# ESP32-C3.net
KiCad netlist of a schematic drawn in Altium Designer
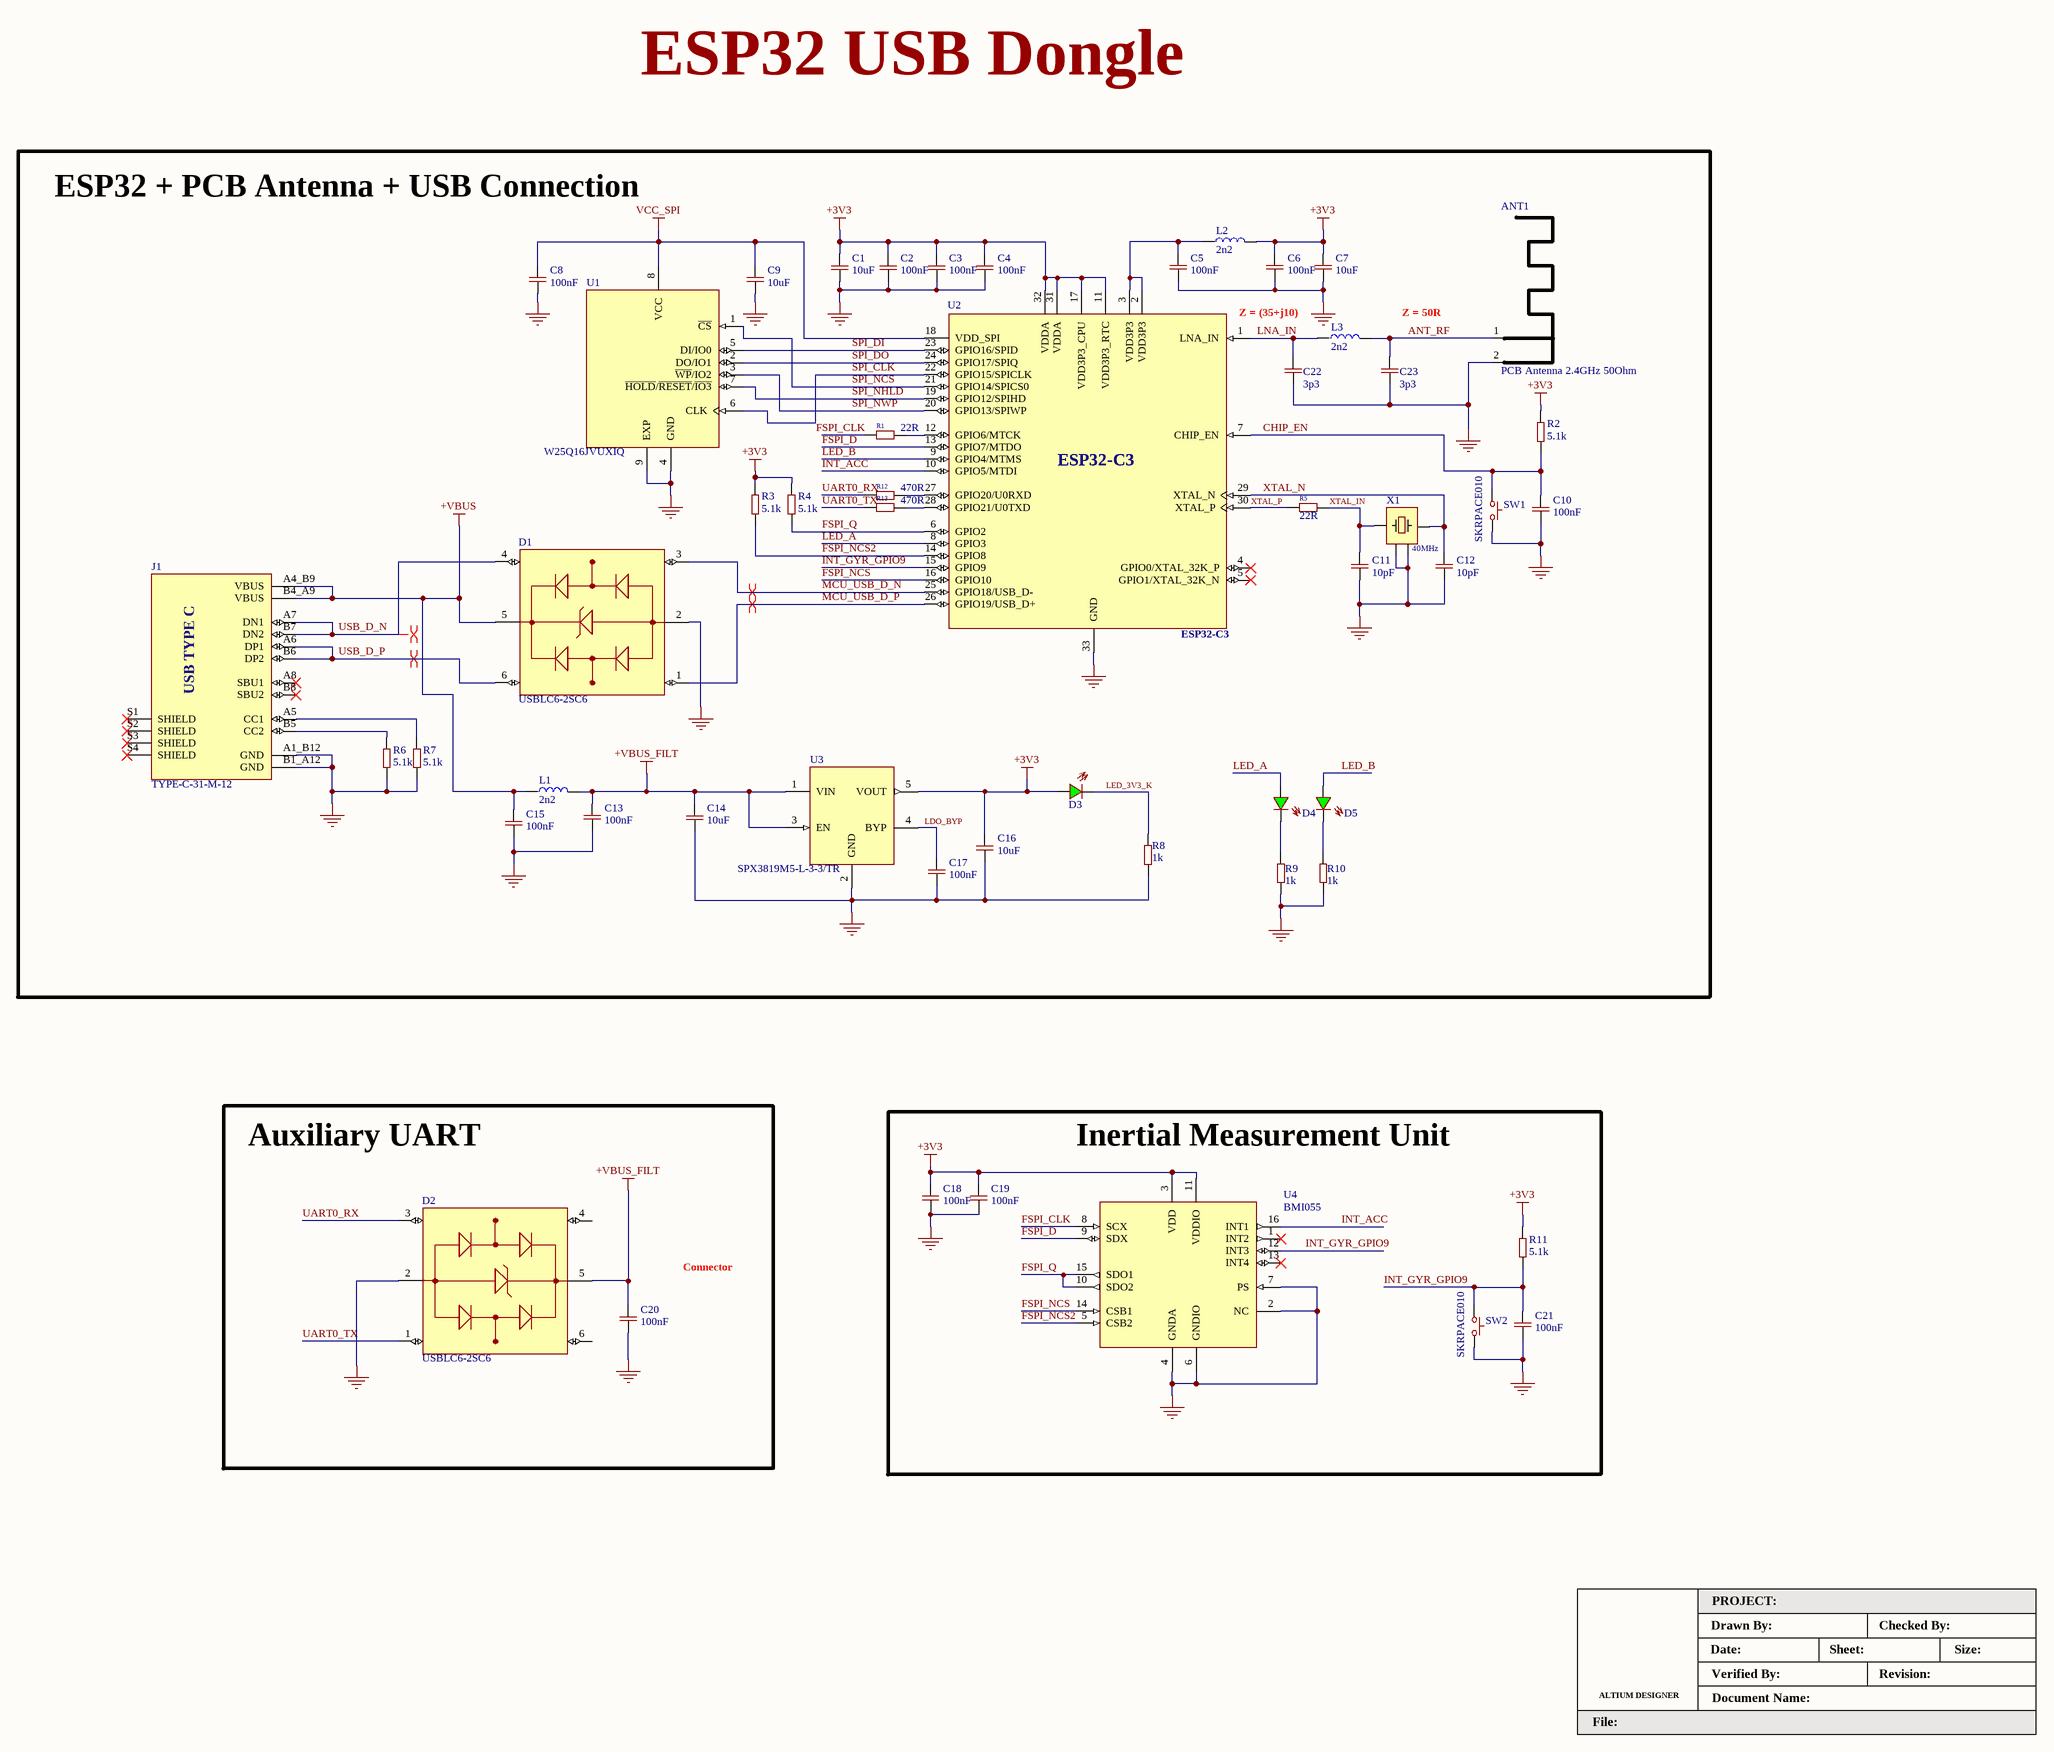
[diagram p0: ESP32-C3.SchDoc]

(export (version "E")
  (design (tool "Eeschema 10.0.6"))
  (components
    (comp (ref "ANT1")
      (value "PCB Antenna 2.4GHz 50Ohm")
      (footprint "ANT_IFA_USB_2_4GHz_50R")
      (description "Inverted F 2.4GHz ISM PCB Antenna 50Ohm")
      (libsource (lib "Schlib_ESP32C3") (part "ANT_IFA_USB_2_4GHz_50R"))
    )
    (comp (ref "C1")
      (value "10uF")
      (footprint "CAP_0603")
      (fields
        (field (name "MANUFACTURER") "Samsung Electro-Mechanics")
        (field (name "MANUFACTURER PART NUMBER") "CL10A106KP8NNNC")
        (field (name "TOLERANCE") "10%")
      )
      (libsource (lib "Schlib_ESP32C3") (part "CAP_0603"))
    )
    (comp (ref "C2")
      (value "100nF")
      (footprint "CAP_0402")
      (fields
        (field (name "MANUFACTURER") "Samsung Electro-Mechanics")
        (field (name "MANUFACTURER PART NUMBER") "CL05B104KO5NNNC")
        (field (name "TOLERANCE") "10%")
      )
      (libsource (lib "Schlib_ESP32C3") (part "CAP_0402"))
    )
    (comp (ref "C3")
      (value "100nF")
      (footprint "CAP_0402")
      (fields
        (field (name "MANUFACTURER") "Samsung Electro-Mechanics")
        (field (name "MANUFACTURER PART NUMBER") "CL05B104KO5NNNC")
        (field (name "TOLERANCE") "10%")
      )
      (libsource (lib "Schlib_ESP32C3") (part "CAP_0402"))
    )
    (comp (ref "C4")
      (value "100nF")
      (footprint "CAP_0402")
      (fields
        (field (name "MANUFACTURER") "Samsung Electro-Mechanics")
        (field (name "MANUFACTURER PART NUMBER") "CL05B104KO5NNNC")
        (field (name "TOLERANCE") "10%")
      )
      (libsource (lib "Schlib_ESP32C3") (part "CAP_0402"))
    )
    (comp (ref "C5")
      (value "100nF")
      (footprint "CAP_0402")
      (fields
        (field (name "MANUFACTURER") "Samsung Electro-Mechanics")
        (field (name "MANUFACTURER PART NUMBER") "CL05B104KO5NNNC")
        (field (name "TOLERANCE") "10%")
      )
      (libsource (lib "Schlib_ESP32C3") (part "CAP_0402"))
    )
    (comp (ref "C6")
      (value "100nF")
      (footprint "CAP_0402")
      (fields
        (field (name "MANUFACTURER") "Samsung Electro-Mechanics")
        (field (name "MANUFACTURER PART NUMBER") "CL05B104KO5NNNC")
        (field (name "TOLERANCE") "10%")
      )
      (libsource (lib "Schlib_ESP32C3") (part "CAP_0402"))
    )
    (comp (ref "C7")
      (value "10uF")
      (footprint "CAP_0603")
      (fields
        (field (name "MANUFACTURER") "Samsung Electro-Mechanics")
        (field (name "MANUFACTURER PART NUMBER") "CL10A106KP8NNNC")
        (field (name "TOLERANCE") "10%")
      )
      (libsource (lib "Schlib_ESP32C3") (part "CAP_0603"))
    )
    (comp (ref "C8")
      (value "100nF")
      (footprint "CAP_0402")
      (fields
        (field (name "MANUFACTURER") "Samsung Electro-Mechanics")
        (field (name "MANUFACTURER PART NUMBER") "CL05B104KO5NNNC")
        (field (name "TOLERANCE") "10%")
      )
      (libsource (lib "Schlib_ESP32C3") (part "CAP_0402"))
    )
    (comp (ref "C9")
      (value "10uF")
      (footprint "CAP_0603")
      (fields
        (field (name "MANUFACTURER") "Samsung Electro-Mechanics")
        (field (name "MANUFACTURER PART NUMBER") "CL10A106KP8NNNC")
        (field (name "TOLERANCE") "10%")
      )
      (libsource (lib "Schlib_ESP32C3") (part "CAP_0603"))
    )
    (comp (ref "C10")
      (value "100nF")
      (footprint "CAP_0402")
      (fields
        (field (name "MANUFACTURER") "Samsung Electro-Mechanics")
        (field (name "MANUFACTURER PART NUMBER") "CL05B104KO5NNNC")
        (field (name "TOLERANCE") "10%")
      )
      (libsource (lib "Schlib_ESP32C3") (part "CAP_0402"))
    )
    (comp (ref "C11")
      (value "10pF")
      (footprint "CAP_0402")
      (fields
        (field (name "MANUFACTURER") "Samsung Electro-Mechanics")
        (field (name "MANUFACTURER PART NUMBER") "CL05C100JB5NNNC")
        (field (name "TOLERANCE") "5%")
      )
      (libsource (lib "Schlib_ESP32C3") (part "CAP_0402"))
    )
    (comp (ref "C12")
      (value "10pF")
      (footprint "CAP_0402")
      (fields
        (field (name "MANUFACTURER") "Samsung Electro-Mechanics")
        (field (name "MANUFACTURER PART NUMBER") "CL05C100JB5NNNC")
        (field (name "TOLERANCE") "5%")
      )
      (libsource (lib "Schlib_ESP32C3") (part "CAP_0402"))
    )
    (comp (ref "C13")
      (value "100nF")
      (footprint "CAP_0402")
      (fields
        (field (name "MANUFACTURER") "Samsung Electro-Mechanics")
        (field (name "MANUFACTURER PART NUMBER") "CL05B104KO5NNNC")
        (field (name "TOLERANCE") "10%")
      )
      (libsource (lib "Schlib_ESP32C3") (part "CAP_0402"))
    )
    (comp (ref "C14")
      (value "10uF")
      (footprint "CAP_0603")
      (fields
        (field (name "MANUFACTURER") "Samsung Electro-Mechanics")
        (field (name "MANUFACTURER PART NUMBER") "CL10A106KP8NNNC")
        (field (name "TOLERANCE") "10%")
      )
      (libsource (lib "Schlib_ESP32C3") (part "CAP_0603"))
    )
    (comp (ref "C15")
      (value "100nF")
      (footprint "CAP_0402")
      (fields
        (field (name "MANUFACTURER") "Samsung Electro-Mechanics")
        (field (name "MANUFACTURER PART NUMBER") "CL05B104KO5NNNC")
        (field (name "TOLERANCE") "10%")
      )
      (libsource (lib "Schlib_ESP32C3") (part "CAP_0402"))
    )
    (comp (ref "C16")
      (value "10uF")
      (footprint "CAP_0603")
      (fields
        (field (name "MANUFACTURER") "Samsung Electro-Mechanics")
        (field (name "MANUFACTURER PART NUMBER") "CL10A106KP8NNNC")
        (field (name "TOLERANCE") "10%")
      )
      (libsource (lib "Schlib_ESP32C3") (part "CAP_0603"))
    )
    (comp (ref "C17")
      (value "100nF")
      (footprint "CAP_0402")
      (fields
        (field (name "MANUFACTURER") "Samsung Electro-Mechanics")
        (field (name "MANUFACTURER PART NUMBER") "CL05B104KO5NNNC")
        (field (name "TOLERANCE") "10%")
      )
      (libsource (lib "Schlib_ESP32C3") (part "CAP_0402"))
    )
    (comp (ref "C18")
      (value "100nF")
      (footprint "CAP_0402")
      (fields
        (field (name "MANUFACTURER") "Samsung Electro-Mechanics")
        (field (name "MANUFACTURER PART NUMBER") "CL05B104KO5NNNC")
        (field (name "TOLERANCE") "10%")
      )
      (libsource (lib "Schlib_ESP32C3") (part "CAP_0402"))
    )
    (comp (ref "C19")
      (value "100nF")
      (footprint "CAP_0402")
      (fields
        (field (name "MANUFACTURER") "Samsung Electro-Mechanics")
        (field (name "MANUFACTURER PART NUMBER") "CL05B104KO5NNNC")
        (field (name "TOLERANCE") "10%")
      )
      (libsource (lib "Schlib_ESP32C3") (part "CAP_0402"))
    )
    (comp (ref "C20")
      (value "100nF")
      (footprint "CAP_0402")
      (fields
        (field (name "MANUFACTURER") "Samsung Electro-Mechanics")
        (field (name "MANUFACTURER PART NUMBER") "CL05B104KO5NNNC")
        (field (name "TOLERANCE") "10%")
      )
      (libsource (lib "Schlib_ESP32C3") (part "CAP_0402"))
    )
    (comp (ref "C21")
      (value "100nF")
      (footprint "CAP_0402")
      (fields
        (field (name "MANUFACTURER") "Samsung Electro-Mechanics")
        (field (name "MANUFACTURER PART NUMBER") "CL05B104KO5NNNC")
        (field (name "TOLERANCE") "10%")
      )
      (libsource (lib "Schlib_ESP32C3") (part "CAP_0402"))
    )
    (comp (ref "C22")
      (value "3p3")
      (footprint "CAP_0402")
      (description "3.3pF 50V Ceramic Capacitor C0G 0402")
      (fields (field (name "MANUFACTURER") "FH") (field (name "MANUFACTURER PART NUMBER") "0402CG3R3C500NT"))
      (libsource (lib "Schlib_ESP32C3") (part "CAP_0402"))
    )
    (comp (ref "C23")
      (value "3p3")
      (footprint "CAP_0402")
      (description "3.3pF 50V Ceramic Capacitor C0G 0402")
      (fields (field (name "MANUFACTURER") "FH") (field (name "MANUFACTURER PART NUMBER") "0402CG3R3C500NT"))
      (libsource (lib "Schlib_ESP32C3") (part "CAP_0402"))
    )
    (comp (ref "D1")
      (value "USBLC6-2SC6")
      (footprint "USBLC6-2SC6")
      (description "STMicroelectronics USBLC6-2SC6 TVS diode surge protection on full tape reel")
      (fields (field (name "MANUFACTURER") "STMicroelectronics"))
      (libsource (lib "Schlib_ESP32C3") (part "USBLC6-2SC6"))
    )
    (comp (ref "D2")
      (value "USBLC6-2SC6")
      (footprint "USBLC6-2SC6")
      (description "STMicroelectronics USBLC6-2SC6 TVS diode surge protection on full tape reel")
      (fields (field (name "MANUFACTURER") "STMicroelectronics"))
      (libsource (lib "Schlib_ESP32C3") (part "USBLC6-2SC6"))
    )
    (comp (ref "D3")
      (value "16-213/GHC-YR1S1/3T")
      (footprint "LED_0402_GREEN_SMD")
      (description "Emerald Green 518nm LED Indication - Discrete 0402")
      (fields (field (name "MANUFACTURER") "EVERLIGHT"))
      (libsource (lib "Schlib_ESP32C3") (part "LED_0402_GREEN_SMD"))
    )
    (comp (ref "D4")
      (value "16-213/GHC-YR1S1/3T")
      (footprint "LED_0402_GREEN_SMD")
      (description "Emerald Green 518nm LED Indication - Discrete 0402")
      (fields (field (name "MANUFACTURER") "EVERLIGHT"))
      (libsource (lib "Schlib_ESP32C3") (part "LED_0402_GREEN_SMD"))
    )
    (comp (ref "D5")
      (value "16-213/GHC-YR1S1/3T")
      (footprint "LED_0402_GREEN_SMD")
      (description "Emerald Green 518nm LED Indication - Discrete 0402")
      (fields (field (name "MANUFACTURER") "EVERLIGHT"))
      (libsource (lib "Schlib_ESP32C3") (part "LED_0402_GREEN_SMD"))
    )
    (comp (ref "J1")
      (value "TYPE-C-31-M-12")
      (footprint "TYPE-C-31-M-12")
      (description "USB-C (USB TYPE-C) Receptacle Connector 16 Position Surface Mount")
      (fields (field (name "MANUFACTURER") "Korean Hroparts Elec"))
      (libsource (lib "Schlib_ESP32C3") (part "TYPE-C-31-M-12"))
    )
    (comp (ref "L1")
      (value "2n2")
      (footprint "IND_SMD_0402")
      (description "IND_SMD_0402")
      (fields
        (field (name "MANUFACTURER") "muRata")
        (field (name "MANUFACTURER PART NUMBER") "LQW15AN2N2G80D")
      )
      (libsource (lib "Schlib_ESP32C3") (part "IND_SMD_0402"))
    )
    (comp (ref "L2")
      (value "2n2")
      (footprint "IND_SMD_0402")
      (description "IND_SMD_0402")
      (fields
        (field (name "MANUFACTURER") "muRata")
        (field (name "MANUFACTURER PART NUMBER") "LQW15AN2N2G80D")
      )
      (libsource (lib "Schlib_ESP32C3") (part "IND_SMD_0402"))
    )
    (comp (ref "L3")
      (value "2n2")
      (footprint "IND_SMD_0402")
      (description "IND_SMD_0402")
      (fields
        (field (name "MANUFACTURER") "muRata")
        (field (name "MANUFACTURER PART NUMBER") "LQW15AN2N2G80D")
      )
      (libsource (lib "Schlib_ESP32C3") (part "IND_SMD_0402"))
    )
    (comp (ref "R1")
      (value "22R")
      (footprint "RES_0402")
      (description "22Ω 62.5mW 50V ±100ppm/℃ Thick Film Resistor ±1% 0402 Chip Resistor - Surface Mount RoHS")
      (fields
        (field (name "MANUFACTURER") "UNI-ROYAL")
        (field (name "MANUFACTURER PART NUMBER") "0402WGF220JTCE")
      )
      (libsource (lib "Schlib_ESP32C3") (part "RES_0402"))
    )
    (comp (ref "R2")
      (value "5.1k")
      (footprint "RES_0402")
      (description "5.1kΩ 62.5mW 50V ±100ppm/℃ Thick Film Resistor ±1% 0402 Chip Resistor - Surface Mount RoHS")
      (fields
        (field (name "MANUFACTURER") "UNI-ROYAL")
        (field (name "MANUFACTURER PART NUMBER") "0402WGF5101TCE")
      )
      (libsource (lib "") (part "RES_0402_1"))
    )
    (comp (ref "R3")
      (value "5.1k")
      (footprint "RES_0402")
      (description "5.1kΩ 62.5mW 50V ±100ppm/℃ Thick Film Resistor ±1% 0402 Chip Resistor - Surface Mount RoHS")
      (fields
        (field (name "MANUFACTURER") "UNI-ROYAL")
        (field (name "MANUFACTURER PART NUMBER") "0402WGF5101TCE")
      )
      (libsource (lib "") (part "RES_0402_1"))
    )
    (comp (ref "R4")
      (value "5.1k")
      (footprint "RES_0402")
      (description "5.1kΩ 62.5mW 50V ±100ppm/℃ Thick Film Resistor ±1% 0402 Chip Resistor - Surface Mount RoHS")
      (fields
        (field (name "MANUFACTURER") "UNI-ROYAL")
        (field (name "MANUFACTURER PART NUMBER") "0402WGF5101TCE")
      )
      (libsource (lib "") (part "RES_0402_1"))
    )
    (comp (ref "R5")
      (value "22R")
      (footprint "RES_0402")
      (description "22Ω 62.5mW 50V ±100ppm/℃ Thick Film Resistor ±1% 0402 Chip Resistor - Surface Mount RoHS")
      (fields
        (field (name "MANUFACTURER") "UNI-ROYAL")
        (field (name "MANUFACTURER PART NUMBER") "0402WGF220JTCE")
      )
      (libsource (lib "Schlib_ESP32C3") (part "RES_0402"))
    )
    (comp (ref "R6")
      (value "5.1k")
      (footprint "RES_0402")
      (description "5.1 kOhms ±5% 0.063W, 1/16W Chip Resistor 0402 (1005 Metric) Moisture Resistant Thick Film")
      (fields
        (field (name "MANUFACTURER") "YAGEO")
        (field (name "MANUFACTURER PART NUMBER") "RC0402JR-075K1L")
      )
      (libsource (lib "") (part "RES_0402_1"))
    )
    (comp (ref "R7")
      (value "5.1k")
      (footprint "RES_0402")
      (description "5.1 kOhms ±5% 0.063W, 1/16W Chip Resistor 0402 (1005 Metric) Moisture Resistant Thick Film")
      (fields
        (field (name "MANUFACTURER") "YAGEO")
        (field (name "MANUFACTURER PART NUMBER") "RC0402JR-075K1L")
      )
      (libsource (lib "") (part "RES_0402_1"))
    )
    (comp (ref "R8")
      (value "1k")
      (footprint "RES_0402")
      (description "1kΩ ±1% 62.5mW 0402 Thick Film Resistor")
      (fields
        (field (name "MANUFACTURER") "UNI-ROYAL")
        (field (name "MANUFACTURER PART NUMBER") "0402WGF1001TCE")
      )
      (libsource (lib "") (part "RES_0402_1"))
    )
    (comp (ref "R9")
      (value "1k")
      (footprint "RES_0402")
      (description "1kΩ ±1% 62.5mW 0402 Thick Film Resistor")
      (fields
        (field (name "MANUFACTURER") "UNI-ROYAL")
        (field (name "MANUFACTURER PART NUMBER") "0402WGF1001TCE")
      )
      (libsource (lib "") (part "RES_0402_1"))
    )
    (comp (ref "R10")
      (value "1k")
      (footprint "RES_0402")
      (description "1kΩ ±1% 62.5mW 0402 Thick Film Resistor")
      (fields
        (field (name "MANUFACTURER") "UNI-ROYAL")
        (field (name "MANUFACTURER PART NUMBER") "0402WGF1001TCE")
      )
      (libsource (lib "") (part "RES_0402_1"))
    )
    (comp (ref "R11")
      (value "5.1k")
      (footprint "RES_0402")
      (description "5.1kΩ 62.5mW 50V ±100ppm/℃ Thick Film Resistor ±1% 0402 Chip Resistor - Surface Mount RoHS")
      (fields
        (field (name "MANUFACTURER") "UNI-ROYAL")
        (field (name "MANUFACTURER PART NUMBER") "0402WGF5101TCE")
      )
      (libsource (lib "") (part "RES_0402_1"))
    )
    (comp (ref "R12")
      (value "470R")
      (footprint "RES_0402")
      (description "470Ω ±1% 62.5mW 0402 Thick Film Resistor")
      (fields
        (field (name "MANUFACTURER") "UNI-ROYAL")
        (field (name "MANUFACTURER PART NUMBER") "0402WGF4700TCE")
      )
      (libsource (lib "Schlib_ESP32C3") (part "RES_0402"))
    )
    (comp (ref "R13")
      (value "470R")
      (footprint "RES_0402")
      (description "470Ω ±1% 62.5mW 0402 Thick Film Resistor")
      (fields
        (field (name "MANUFACTURER") "UNI-ROYAL")
        (field (name "MANUFACTURER PART NUMBER") "0402WGF4700TCE")
      )
      (libsource (lib "Schlib_ESP32C3") (part "RES_0402"))
    )
    (comp (ref "SW1")
      (value "SKRPACE010")
      (footprint "Tactile Switch")
      (description "Switch Tactile N.O. SPST Button J-Bend 0.05A 16VDC 2.55N SMD T/R")
      (fields (field (name "MANUFACTURER") "ALPS"))
      (libsource (lib "Schlib_ESP32C3") (part "Tactile Switch"))
    )
    (comp (ref "SW2")
      (value "SKRPACE010")
      (footprint "Tactile Switch")
      (description "Switch Tactile N.O. SPST Button J-Bend 0.05A 16VDC 2.55N SMD T/R")
      (fields (field (name "MANUFACTURER") "ALPS"))
      (libsource (lib "Schlib_ESP32C3") (part "Tactile Switch"))
    )
    (comp (ref "U1")
      (value "W25Q16JVUXIQ")
      (footprint "W25Q16JVUXIQ")
      (description "NOR Flash Serial (SPI, Dual SPI, Quad SPI) 3V/3.3V 16M-bit 2M x 8 6ns 8-Pin USON EP T/R")
      (fields
        (field (name "MANUFACTURER") "Winbond")
        (field (name "MANUFACTURER PART NUMBER") "W25Q16JVUXIQ TR")
      )
      (libsource (lib "Schlib_ESP32C3") (part "W25Q16JVUXIQ"))
    )
    (comp (ref "U2")
      (value "ESP32-C3")
      (footprint "ESP32-C3")
      (description "400KB 22 3V~3.6V RISC-V 160MHz QFN-32-EP(5x5) Microcontroller Units (MCUs/MPUs/SOCs) ROHS")
      (fields (field (name "MANUFACTURER") "Espressif Systems"))
      (libsource (lib "Schlib_ESP32C3") (part "ESP32-C3"))
    )
    (comp (ref "U3")
      (value "SPX3819M5-L-3-3/TR")
      (footprint "SPX3819M5-L-3-3/TR")
      (description "SPX3819 Series 3.3 V 500 mA Fixed Output SMT LDO Regulator - SOT-23-5")
      (fields (field (name "MANUFACTURER") "MaxLinear"))
      (libsource (lib "Schlib_ESP32C3") (part "SPX3819M5-L-3-3/TR"))
    )
    (comp (ref "U4")
      (value "BMI055")
      (footprint "BMI055")
      (description "LGA-16(3x4.5) Accelerometers RoHS")
      (fields (field (name "MANUFACTURER") "Bosch"))
      (libsource (lib "Schlib_ESP32C3") (part "BMI055"))
    )
    (comp (ref "X1")
      (value "40MHz")
      (footprint "XTAL_40MHz_2520")
      (description "Crystal 40MHz ±10ppm (Tol) ±20ppm (Stability) 9pF FUND 40Ohm 4-Pin Ultra Mini-CSMD T/R")
      (fields
        (field (name "MANUFACTURER") "Epson")
        (field (name "MANUFACTURER PART NUMBER") "FA-20H 40.0000MF20X-AC3")
      )
      (libsource (lib "Schlib_ESP32C3") (part "XTAL_40MHz_2520"))
    )
  )
  (nets
    (net (code "1") (name "+3V3") (class "Default")
      (node (ref "C1") (pin "2") (pinfunction "2_2") (pintype "passive"))
      (node (ref "C16") (pin "2") (pinfunction "2_2") (pintype "passive"))
      (node (ref "C18") (pin "2") (pinfunction "2_2") (pintype "passive"))
      (node (ref "C19") (pin "2") (pinfunction "2_2") (pintype "passive"))
      (node (ref "C2") (pin "2") (pinfunction "2_2") (pintype "passive"))
      (node (ref "C3") (pin "2") (pinfunction "2_2") (pintype "passive"))
      (node (ref "C4") (pin "2") (pinfunction "2_2") (pintype "passive"))
      (node (ref "C6") (pin "2") (pinfunction "2_2") (pintype "passive"))
      (node (ref "C7") (pin "2") (pinfunction "2_2") (pintype "passive"))
      (node (ref "D3") (pin "1") (pinfunction "1_1") (pintype "passive"))
      (node (ref "L2") (pin "2") (pinfunction "2_2") (pintype "passive"))
      (node (ref "R11") (pin "2") (pinfunction "2_2") (pintype "passive"))
      (node (ref "R2") (pin "2") (pinfunction "2_2") (pintype "passive"))
      (node (ref "R3") (pin "2") (pinfunction "2_2") (pintype "passive"))
      (node (ref "R4") (pin "2") (pinfunction "2_2") (pintype "passive"))
      (node (ref "U2") (pin "11") (pinfunction "VDD3P3_RTC_11") (pintype "power_in"))
      (node (ref "U2") (pin "17") (pinfunction "VDD3P3_CPU_17") (pintype "power_in"))
      (node (ref "U2") (pin "31") (pinfunction "VDDA_31") (pintype "power_in"))
      (node (ref "U2") (pin "32") (pinfunction "VDDA_32") (pintype "power_in"))
      (node (ref "U3") (pin "5") (pinfunction "VOUT_5") (pintype "output"))
      (node (ref "U4") (pin "11") (pinfunction "VDDIO_11") (pintype "power_in"))
      (node (ref "U4") (pin "3") (pinfunction "VDD_3") (pintype "power_in"))
    )
    (net (code "2") (name "+VBUS") (class "Default")
      (node (ref "C15") (pin "2") (pinfunction "2_2") (pintype "passive"))
      (node (ref "D1") (pin "5") (pinfunction "VBUS_5") (pintype "power_in"))
      (node (ref "J1") (pin "A4_B9") (pinfunction "VBUS_A4_B9") (pintype "power_in"))
      (node (ref "J1") (pin "B4_A9") (pinfunction "VBUS_B4_A9") (pintype "power_in"))
      (node (ref "L1") (pin "1") (pinfunction "1_1") (pintype "passive"))
    )
    (net (code "3") (name "+VBUS_FILT") (class "Default")
      (node (ref "C13") (pin "2") (pinfunction "2_2") (pintype "passive"))
      (node (ref "C14") (pin "2") (pinfunction "2_2") (pintype "passive"))
      (node (ref "C20") (pin "2") (pinfunction "2_2") (pintype "passive"))
      (node (ref "D2") (pin "5") (pinfunction "VBUS_5") (pintype "power_in"))
      (node (ref "L1") (pin "2") (pinfunction "2_2") (pintype "passive"))
      (node (ref "U3") (pin "1") (pinfunction "VIN_1") (pintype "power_in"))
      (node (ref "U3") (pin "3") (pinfunction "EN_3") (pintype "input"))
    )
    (net (code "4") (name "/ANT_RF") (class "Default")
      (node (ref "ANT1") (pin "1") (pinfunction "RF_1") (pintype "passive"))
      (node (ref "C23") (pin "2") (pinfunction "2_2") (pintype "passive"))
      (node (ref "L3") (pin "2") (pinfunction "2_2") (pintype "passive"))
    )
    (net (code "5") (name "/CHIP_EN") (class "Default")
      (node (ref "C10") (pin "2") (pinfunction "2_2") (pintype "passive"))
      (node (ref "R2") (pin "1") (pinfunction "1_1") (pintype "passive"))
      (node (ref "SW1") (pin "1") (pinfunction "1_1") (pintype "passive"))
      (node (ref "U2") (pin "7") (pinfunction "CHIP_EN_7") (pintype "input"))
    )
    (net (code "6") (name "/FSPI_CLK") (class "Default")
      (node (ref "U4") (pin "8") (pinfunction "SCX_8") (pintype "input"))
    )
    (net (code "7") (name "/FSPI_D") (class "Default")
      (node (ref "U2") (pin "13") (pinfunction "GPIO7/MTDO_13") (pintype "bidirectional"))
      (node (ref "U4") (pin "9") (pinfunction "SDX_9") (pintype "bidirectional"))
    )
    (net (code "8") (name "/FSPI_NCS") (class "Default")
      (node (ref "U2") (pin "16") (pinfunction "GPIO10_16") (pintype "bidirectional"))
      (node (ref "U4") (pin "14") (pinfunction "CSB1_14") (pintype "input"))
    )
    (net (code "9") (name "/FSPI_NCS2") (class "Default")
      (node (ref "R3") (pin "1") (pinfunction "1_1") (pintype "passive"))
      (node (ref "U2") (pin "14") (pinfunction "GPIO8_14") (pintype "bidirectional"))
      (node (ref "U4") (pin "5") (pinfunction "CSB2_5") (pintype "input"))
    )
    (net (code "10") (name "/FSPI_Q") (class "Default")
      (node (ref "R4") (pin "1") (pinfunction "1_1") (pintype "passive"))
      (node (ref "U2") (pin "6") (pinfunction "GPIO2_6") (pintype "bidirectional"))
      (node (ref "U4") (pin "10") (pinfunction "SDO2_10") (pintype "output"))
      (node (ref "U4") (pin "15") (pinfunction "SDO1_15") (pintype "output"))
    )
    (net (code "11") (name "/INT_ACC") (class "Default")
      (node (ref "U2") (pin "10") (pinfunction "GPIO5/MTDI_10") (pintype "bidirectional"))
      (node (ref "U4") (pin "16") (pinfunction "INT1_16") (pintype "output"))
    )
    (net (code "12") (name "/INT_GYR_GPIO9") (class "Default")
      (node (ref "C21") (pin "2") (pinfunction "2_2") (pintype "passive"))
      (node (ref "R11") (pin "1") (pinfunction "1_1") (pintype "passive"))
      (node (ref "SW2") (pin "1") (pinfunction "1_1") (pintype "passive"))
      (node (ref "U2") (pin "15") (pinfunction "GPIO9_15") (pintype "bidirectional"))
      (node (ref "U4") (pin "12") (pinfunction "INT3_12") (pintype "bidirectional"))
    )
    (net (code "13") (name "/LDO_BYP") (class "Default")
      (node (ref "C17") (pin "2") (pinfunction "2_2") (pintype "passive"))
      (node (ref "U3") (pin "4") (pinfunction "BYP_4") (pintype "passive"))
    )
    (net (code "14") (name "/LED_3V3_K") (class "Default")
      (node (ref "D3") (pin "2") (pinfunction "2_2") (pintype "passive"))
      (node (ref "R8") (pin "2") (pinfunction "2_2") (pintype "passive"))
    )
    (net (code "15") (name "/LED_A") (class "Default")
      (node (ref "D4") (pin "1") (pinfunction "1_1") (pintype "passive"))
      (node (ref "U2") (pin "8") (pinfunction "GPIO3_8") (pintype "bidirectional"))
    )
    (net (code "16") (name "/LED_B") (class "Default")
      (node (ref "D5") (pin "1") (pinfunction "1_1") (pintype "passive"))
      (node (ref "U2") (pin "9") (pinfunction "GPIO4/MTMS_9") (pintype "bidirectional"))
    )
    (net (code "17") (name "/LNA_IN") (class "Default")
      (node (ref "C22") (pin "2") (pinfunction "2_2") (pintype "passive"))
      (node (ref "L3") (pin "1") (pinfunction "1_1") (pintype "passive"))
      (node (ref "U2") (pin "1") (pinfunction "LNA_IN_1") (pintype "input"))
    )
    (net (code "18") (name "/MCU_USB_D_N") (class "Default")
      (node (ref "D1") (pin "3") (pinfunction "I/O2_IN_3") (pintype "bidirectional"))
      (node (ref "U2") (pin "25") (pinfunction "GPIO18/USB_D-_25") (pintype "bidirectional"))
    )
    (net (code "19") (name "/MCU_USB_D_P") (class "Default")
      (node (ref "D1") (pin "1") (pinfunction "I/O1_IN_1") (pintype "bidirectional"))
      (node (ref "U2") (pin "26") (pinfunction "GPIO19/USB_D+_26") (pintype "bidirectional"))
    )
    (net (code "20") (name "/SPI_CLK") (class "Default")
      (node (ref "U1") (pin "6") (pinfunction "CLK_6") (pintype "input"))
      (node (ref "U2") (pin "22") (pinfunction "GPIO15/SPICLK_22") (pintype "bidirectional"))
    )
    (net (code "21") (name "/SPI_DI") (class "Default")
      (node (ref "U1") (pin "5") (pinfunction "DI/IO0_5") (pintype "bidirectional"))
      (node (ref "U2") (pin "23") (pinfunction "GPIO16/SPID_23") (pintype "bidirectional"))
    )
    (net (code "22") (name "/SPI_DO") (class "Default")
      (node (ref "U1") (pin "2") (pinfunction "DO/IO1_2") (pintype "bidirectional"))
      (node (ref "U2") (pin "24") (pinfunction "GPIO17/SPIQ_24") (pintype "bidirectional"))
    )
    (net (code "23") (name "/SPI_NCS") (class "Default")
      (node (ref "U1") (pin "1") (pinfunction "~{CS}_1") (pintype "input"))
      (node (ref "U2") (pin "21") (pinfunction "GPIO14/SPICS0_21") (pintype "bidirectional"))
    )
    (net (code "24") (name "/SPI_NHLD") (class "Default")
      (node (ref "U1") (pin "7") (pinfunction "~{HOLD}/~{RESET}/~{IO3}_7") (pintype "bidirectional"))
      (node (ref "U2") (pin "19") (pinfunction "GPIO12/SPIHD_19") (pintype "bidirectional"))
    )
    (net (code "25") (name "/SPI_NWP") (class "Default")
      (node (ref "U1") (pin "3") (pinfunction "~{WP}/IO2_3") (pintype "bidirectional"))
      (node (ref "U2") (pin "20") (pinfunction "GPIO13/SPIWP_20") (pintype "bidirectional"))
    )
    (net (code "26") (name "/UART0_RX") (class "Default")
      (node (ref "D2") (pin "3") (pinfunction "I/O2_IN_3") (pintype "bidirectional"))
      (node (ref "R12") (pin "1") (pinfunction "1_1") (pintype "passive"))
    )
    (net (code "27") (name "/UART0_TX") (class "Default")
      (node (ref "D2") (pin "1") (pinfunction "I/O1_IN_1") (pintype "bidirectional"))
      (node (ref "R13") (pin "1") (pinfunction "1_1") (pintype "passive"))
    )
    (net (code "28") (name "/USB_D_N") (class "Default")
      (node (ref "D1") (pin "4") (pinfunction "I/O2_OUT_4") (pintype "bidirectional"))
      (node (ref "J1") (pin "A7") (pinfunction "DN1_A7") (pintype "bidirectional"))
      (node (ref "J1") (pin "B7") (pinfunction "DN2_B7") (pintype "bidirectional"))
    )
    (net (code "29") (name "/USB_D_P") (class "Default")
      (node (ref "D1") (pin "6") (pinfunction "I/O1_OUT_6") (pintype "bidirectional"))
      (node (ref "J1") (pin "A6") (pinfunction "DP1_A6") (pintype "bidirectional"))
      (node (ref "J1") (pin "B6") (pinfunction "DP2_B6") (pintype "bidirectional"))
    )
    (net (code "30") (name "/XTAL_IN") (class "Default")
      (node (ref "C11") (pin "2") (pinfunction "2_2") (pintype "passive"))
      (node (ref "R5") (pin "2") (pinfunction "2_2") (pintype "passive"))
      (node (ref "X1") (pin "1") (pinfunction "1_1") (pintype "passive"))
    )
    (net (code "31") (name "/XTAL_N") (class "Default")
      (node (ref "C12") (pin "2") (pinfunction "2_2") (pintype "passive"))
      (node (ref "U2") (pin "29") (pinfunction "XTAL_N_29") (pintype "input"))
      (node (ref "X1") (pin "3") (pinfunction "3_3") (pintype "passive"))
    )
    (net (code "32") (name "/XTAL_P") (class "Default")
      (node (ref "R5") (pin "1") (pinfunction "1_1") (pintype "passive"))
      (node (ref "U2") (pin "30") (pinfunction "XTAL_P_30") (pintype "input"))
    )
    (net (code "33") (name "GND") (class "Default")
      (node (ref "ANT1") (pin "2") (pinfunction "GND_2") (pintype "passive"))
      (node (ref "C1") (pin "1") (pinfunction "1_1") (pintype "passive"))
      (node (ref "C10") (pin "1") (pinfunction "1_1") (pintype "passive"))
      (node (ref "C11") (pin "1") (pinfunction "1_1") (pintype "passive"))
      (node (ref "C12") (pin "1") (pinfunction "1_1") (pintype "passive"))
      (node (ref "C13") (pin "1") (pinfunction "1_1") (pintype "passive"))
      (node (ref "C14") (pin "1") (pinfunction "1_1") (pintype "passive"))
      (node (ref "C15") (pin "1") (pinfunction "1_1") (pintype "passive"))
      (node (ref "C16") (pin "1") (pinfunction "1_1") (pintype "passive"))
      (node (ref "C17") (pin "1") (pinfunction "1_1") (pintype "passive"))
      (node (ref "C18") (pin "1") (pinfunction "1_1") (pintype "passive"))
      (node (ref "C19") (pin "1") (pinfunction "1_1") (pintype "passive"))
      (node (ref "C2") (pin "1") (pinfunction "1_1") (pintype "passive"))
      (node (ref "C20") (pin "1") (pinfunction "1_1") (pintype "passive"))
      (node (ref "C21") (pin "1") (pinfunction "1_1") (pintype "passive"))
      (node (ref "C22") (pin "1") (pinfunction "1_1") (pintype "passive"))
      (node (ref "C23") (pin "1") (pinfunction "1_1") (pintype "passive"))
      (node (ref "C3") (pin "1") (pinfunction "1_1") (pintype "passive"))
      (node (ref "C4") (pin "1") (pinfunction "1_1") (pintype "passive"))
      (node (ref "C5") (pin "1") (pinfunction "1_1") (pintype "passive"))
      (node (ref "C6") (pin "1") (pinfunction "1_1") (pintype "passive"))
      (node (ref "C7") (pin "1") (pinfunction "1_1") (pintype "passive"))
      (node (ref "C8") (pin "1") (pinfunction "1_1") (pintype "passive"))
      (node (ref "C9") (pin "1") (pinfunction "1_1") (pintype "passive"))
      (node (ref "D1") (pin "2") (pinfunction "GND_2") (pintype "power_in"))
      (node (ref "D2") (pin "2") (pinfunction "GND_2") (pintype "power_in"))
      (node (ref "J1") (pin "A1_B12") (pinfunction "GND_A1_B12") (pintype "power_in"))
      (node (ref "J1") (pin "B1_A12") (pinfunction "GND_B1_A12") (pintype "power_in"))
      (node (ref "R10") (pin "1") (pinfunction "1_1") (pintype "passive"))
      (node (ref "R6") (pin "1") (pinfunction "1_1") (pintype "passive"))
      (node (ref "R7") (pin "1") (pinfunction "1_1") (pintype "passive"))
      (node (ref "R8") (pin "1") (pinfunction "1_1") (pintype "passive"))
      (node (ref "R9") (pin "1") (pinfunction "1_1") (pintype "passive"))
      (node (ref "SW1") (pin "2") (pinfunction "2_2") (pintype "passive"))
      (node (ref "SW2") (pin "2") (pinfunction "2_2") (pintype "passive"))
      (node (ref "U1") (pin "4") (pinfunction "GND_4") (pintype "power_in"))
      (node (ref "U1") (pin "9") (pinfunction "EXP_9") (pintype "passive"))
      (node (ref "U2") (pin "33") (pinfunction "GND_33") (pintype "power_in"))
      (node (ref "U3") (pin "2") (pinfunction "GND_2") (pintype "passive"))
      (node (ref "U4") (pin "2") (pinfunction "NC_2") (pintype "passive"))
      (node (ref "U4") (pin "4") (pinfunction "GNDA_4") (pintype "passive"))
      (node (ref "U4") (pin "6") (pinfunction "GNDIO_6") (pintype "passive"))
      (node (ref "U4") (pin "7") (pinfunction "PS_7") (pintype "input"))
      (node (ref "X1") (pin "2") (pinfunction "2_2") (pintype "passive"))
      (node (ref "X1") (pin "4") (pinfunction "4_4") (pintype "passive"))
    )
    (net (code "34") (name "Net-(C5-Pad2)") (class "Default")
      (node (ref "C5") (pin "2") (pinfunction "2_2") (pintype "passive"))
      (node (ref "L2") (pin "1") (pinfunction "1_1") (pintype "passive"))
      (node (ref "U2") (pin "2") (pinfunction "VDD3P3_2") (pintype "power_in"))
      (node (ref "U2") (pin "3") (pinfunction "VDD3P3_3") (pintype "power_in"))
    )
    (net (code "35") (name "Net-(D4-Pad2)") (class "Default")
      (node (ref "D4") (pin "2") (pinfunction "2_2") (pintype "passive"))
      (node (ref "R9") (pin "2") (pinfunction "2_2") (pintype "passive"))
    )
    (net (code "36") (name "Net-(D5-Pad2)") (class "Default")
      (node (ref "D5") (pin "2") (pinfunction "2_2") (pintype "passive"))
      (node (ref "R10") (pin "2") (pinfunction "2_2") (pintype "passive"))
    )
    (net (code "37") (name "Net-(J1-CC1)") (class "Default")
      (node (ref "J1") (pin "A5") (pinfunction "CC1_A5") (pintype "bidirectional"))
      (node (ref "R7") (pin "2") (pinfunction "2_2") (pintype "passive"))
    )
    (net (code "38") (name "Net-(J1-CC2)") (class "Default")
      (node (ref "J1") (pin "B5") (pinfunction "CC2_B5") (pintype "bidirectional"))
      (node (ref "R6") (pin "2") (pinfunction "2_2") (pintype "passive"))
    )
    (net (code "39") (name "Net-(U2-GPIO6{slash}MTCK)") (class "Default")
      (node (ref "R1") (pin "2") (pinfunction "2_2") (pintype "passive"))
      (node (ref "U2") (pin "12") (pinfunction "GPIO6/MTCK_12") (pintype "bidirectional"))
    )
    (net (code "40") (name "Net-(U2-GPIO20{slash}U0RXD)") (class "Default")
      (node (ref "R12") (pin "2") (pinfunction "2_2") (pintype "passive"))
      (node (ref "U2") (pin "27") (pinfunction "GPIO20/U0RXD_27") (pintype "bidirectional"))
    )
    (net (code "41") (name "Net-(U2-GPIO21{slash}U0TXD)") (class "Default")
      (node (ref "R13") (pin "2") (pinfunction "2_2") (pintype "passive"))
      (node (ref "U2") (pin "28") (pinfunction "GPIO21/U0TXD_28") (pintype "bidirectional"))
    )
    (net (code "42") (name "VCC_SPI") (class "Default")
      (node (ref "C8") (pin "2") (pinfunction "2_2") (pintype "passive"))
      (node (ref "C9") (pin "2") (pinfunction "2_2") (pintype "passive"))
      (node (ref "U1") (pin "8") (pinfunction "VCC_8") (pintype "power_in"))
      (node (ref "U2") (pin "18") (pinfunction "VDD_SPI_18") (pintype "power_in"))
    )
    (net (code "43") (name "unconnected-(D2-I{slash}O1_OUT-Pad6)") (class "Default")
      (node (ref "D2") (pin "6") (pinfunction "I/O1_OUT_6") (pintype "bidirectional"))
    )
    (net (code "44") (name "unconnected-(D2-I{slash}O2_OUT-Pad4)") (class "Default")
      (node (ref "D2") (pin "4") (pinfunction "I/O2_OUT_4") (pintype "bidirectional"))
    )
    (net (code "45") (name "unconnected-(J1-SBU1-PadA8)") (class "Default")
      (node (ref "J1") (pin "A8") (pinfunction "SBU1_A8") (pintype "bidirectional+no_connect"))
    )
    (net (code "46") (name "unconnected-(J1-SBU2-PadB8)") (class "Default")
      (node (ref "J1") (pin "B8") (pinfunction "SBU2_B8") (pintype "bidirectional+no_connect"))
    )
    (net (code "47") (name "unconnected-(J1-SHIELD-PadS1)") (class "Default")
      (node (ref "J1") (pin "S1") (pinfunction "SHIELD_S1") (pintype "passive+no_connect"))
    )
    (net (code "48") (name "unconnected-(J1-SHIELD-PadS2)") (class "Default")
      (node (ref "J1") (pin "S2") (pinfunction "SHIELD_S2") (pintype "passive+no_connect"))
    )
    (net (code "49") (name "unconnected-(J1-SHIELD-PadS3)") (class "Default")
      (node (ref "J1") (pin "S3") (pinfunction "SHIELD_S3") (pintype "passive+no_connect"))
    )
    (net (code "50") (name "unconnected-(J1-SHIELD-PadS4)") (class "Default")
      (node (ref "J1") (pin "S4") (pinfunction "SHIELD_S4") (pintype "passive+no_connect"))
    )
    (net (code "51") (name "unconnected-(R1-Pad1)") (class "Default")
      (node (ref "R1") (pin "1") (pinfunction "1_1") (pintype "passive"))
    )
    (net (code "52") (name "unconnected-(U2-GPIO0{slash}XTAL_32K_P-Pad4)") (class "Default")
      (node (ref "U2") (pin "4") (pinfunction "GPIO0/XTAL_32K_P_4") (pintype "bidirectional+no_connect"))
    )
    (net (code "53") (name "unconnected-(U2-GPIO1{slash}XTAL_32K_N-Pad5)") (class "Default")
      (node (ref "U2") (pin "5") (pinfunction "GPIO1/XTAL_32K_N_5") (pintype "bidirectional+no_connect"))
    )
    (net (code "54") (name "unconnected-(U4-INT2-Pad1)") (class "Default")
      (node (ref "U4") (pin "1") (pinfunction "INT2_1") (pintype "output+no_connect"))
    )
    (net (code "55") (name "unconnected-(U4-INT4-Pad13)") (class "Default")
      (node (ref "U4") (pin "13") (pinfunction "INT4_13") (pintype "bidirectional+no_connect"))
    )
  )
)
